# Audio.net
KiCad netlist of a schematic drawn in Altium Designer
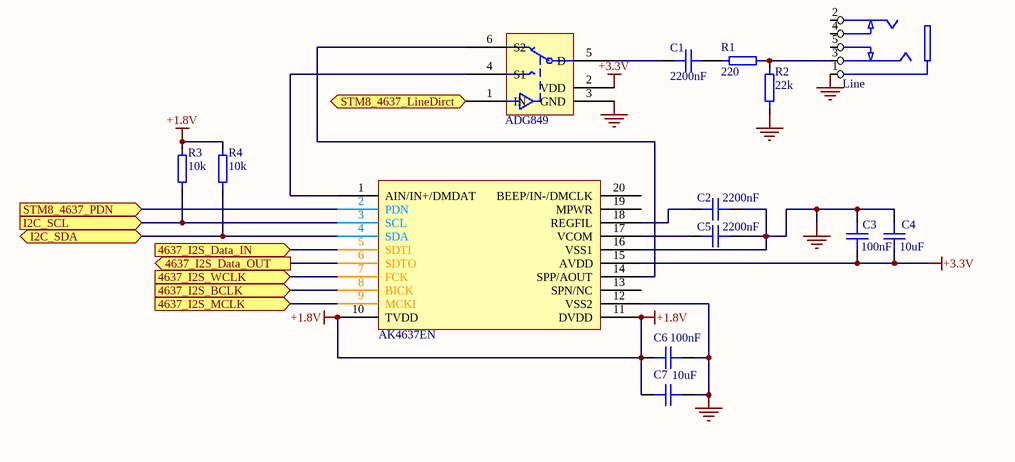
[diagram p0: Audio.SchDoc]

(export (version "E")
  (design (tool "Eeschema 10.0.6"))
  (components
    (comp (ref "ADG849") (value "ADG849") (footprint "ADG849") (libsource (lib "WPU161C") (part "ADG849")))
    (comp (ref "AK4637EN")
      (value "AK4637EN")
      (footprint "AK4637EN")
      (libsource (lib "WPU161C") (part "AK4637EN"))
    )
    (comp (ref "C1")
      (value "2200nF")
      (footprint "SMD 0402")
      (fields (field (name "Comment") "Capacity SMD"))
      (libsource (lib "WPU161C") (part "Capacity SMD"))
    )
    (comp (ref "C2")
      (value "2200nF")
      (footprint "SMD 0402")
      (fields (field (name "Comment") "Capacity SMD"))
      (libsource (lib "WPU161C") (part "Capacity SMD"))
    )
    (comp (ref "C3")
      (value "100nF")
      (footprint "SMD 0402")
      (fields (field (name "Comment") "Capacity SMD"))
      (libsource (lib "WPU161C") (part "Capacity SMD"))
    )
    (comp (ref "C4")
      (value "10uF")
      (footprint "SMD 0402")
      (fields (field (name "Comment") "Capacity SMD"))
      (libsource (lib "WPU161C") (part "Capacity SMD"))
    )
    (comp (ref "C5")
      (value "2200nF")
      (footprint "SMD 0402")
      (fields (field (name "Comment") "Capacity SMD"))
      (libsource (lib "WPU161C") (part "Capacity SMD"))
    )
    (comp (ref "C6")
      (value "100nF")
      (footprint "SMD 0402")
      (fields (field (name "Comment") "Capacity SMD"))
      (libsource (lib "WPU161C") (part "Capacity SMD"))
    )
    (comp (ref "C7")
      (value "10uF")
      (footprint "SMD 0402")
      (fields (field (name "Comment") "Capacity SMD"))
      (libsource (lib "WPU161C") (part "Capacity SMD"))
    )
    (comp (ref "Line")
      (value "Audio Jack")
      (footprint "Audio Jack PJ-328")
      (libsource (lib "WPU161C") (part "Audio Jack PJ-328"))
    )
    (comp (ref "R1")
      (value "220")
      (footprint "SMD 0402")
      (fields (field (name "Comment") "Resistor SMD"))
      (libsource (lib "WPU161C") (part "Resistor SMD"))
    )
    (comp (ref "R2")
      (value "22k")
      (footprint "SMD 0402")
      (fields (field (name "Comment") "Resistor SMD"))
      (libsource (lib "WPU161C") (part "Resistor SMD"))
    )
    (comp (ref "R3")
      (value "10k")
      (footprint "SMD 0402")
      (fields (field (name "Comment") "Resistor SMD"))
      (libsource (lib "WPU161C") (part "Resistor SMD"))
    )
    (comp (ref "R4")
      (value "10k")
      (footprint "SMD 0402")
      (fields (field (name "Comment") "Resistor SMD"))
      (libsource (lib "WPU161C") (part "Resistor SMD"))
    )
  )
  (nets
    (net (code "1") (name "+1.8V") (class "Default")
      (node (ref "AK4637EN") (pin "10") (pinfunction "TVDD_10") (pintype "passive"))
      (node (ref "AK4637EN") (pin "11") (pinfunction "DVDD_11") (pintype "passive"))
      (node (ref "C6") (pin "1") (pintype "passive"))
      (node (ref "C7") (pin "1") (pintype "passive"))
      (node (ref "R3") (pin "2") (pintype "passive"))
      (node (ref "R4") (pin "2") (pintype "passive"))
    )
    (net (code "2") (name "+3.3V") (class "Default")
      (node (ref "ADG849") (pin "2") (pinfunction "VDD_2") (pintype "passive"))
      (node (ref "AK4637EN") (pin "15") (pinfunction "AVDD_15") (pintype "passive"))
      (node (ref "C3") (pin "1") (pintype "passive"))
      (node (ref "C4") (pin "1") (pintype "passive"))
    )
    (net (code "3") (name "/4637_I2S_BCLK") (class "Default")
      (node (ref "AK4637EN") (pin "8") (pinfunction "BICK_8") (pintype "passive"))
    )
    (net (code "4") (name "/4637_I2S_Data_IN") (class "Default")
      (node (ref "AK4637EN") (pin "5") (pinfunction "SDTI_5") (pintype "passive"))
    )
    (net (code "5") (name "/4637_I2S_Data_OUT") (class "Default")
      (node (ref "AK4637EN") (pin "6") (pinfunction "SDTO_6") (pintype "passive"))
    )
    (net (code "6") (name "/4637_I2S_MCLK") (class "Default")
      (node (ref "AK4637EN") (pin "9") (pinfunction "MCKI_9") (pintype "passive"))
    )
    (net (code "7") (name "/4637_I2S_WCLK") (class "Default")
      (node (ref "AK4637EN") (pin "7") (pinfunction "FCK_7") (pintype "passive"))
    )
    (net (code "8") (name "/I2C_SCL") (class "Default")
      (node (ref "AK4637EN") (pin "3") (pinfunction "SCL_3") (pintype "passive"))
      (node (ref "R3") (pin "1") (pintype "passive"))
    )
    (net (code "9") (name "/I2C_SDA") (class "Default")
      (node (ref "AK4637EN") (pin "4") (pinfunction "SDA_4") (pintype "passive"))
      (node (ref "R4") (pin "1") (pintype "passive"))
    )
    (net (code "10") (name "/STM8_4637_LineDirct") (class "Default")
      (node (ref "ADG849") (pin "1") (pinfunction "IN_1") (pintype "passive"))
    )
    (net (code "11") (name "/STM8_4637_PDN") (class "Default")
      (node (ref "AK4637EN") (pin "2") (pinfunction "PDN_2") (pintype "passive"))
    )
    (net (code "12") (name "GND") (class "Default")
      (node (ref "ADG849") (pin "3") (pinfunction "GND_3") (pintype "passive"))
      (node (ref "AK4637EN") (pin "12") (pinfunction "VSS2_12") (pintype "passive"))
      (node (ref "AK4637EN") (pin "16") (pinfunction "VSS1_16") (pintype "passive"))
      (node (ref "C2") (pin "2") (pintype "passive"))
      (node (ref "C3") (pin "2") (pintype "passive"))
      (node (ref "C4") (pin "2") (pintype "passive"))
      (node (ref "C5") (pin "2") (pintype "passive"))
      (node (ref "C6") (pin "2") (pintype "passive"))
      (node (ref "C7") (pin "2") (pintype "passive"))
      (node (ref "Line") (pin "1") (pinfunction "GND_1") (pintype "passive"))
      (node (ref "R2") (pin "1") (pintype "passive"))
    )
    (net (code "13") (name "Net-(ADG849-D)") (class "Default")
      (node (ref "ADG849") (pin "5") (pinfunction "D_5") (pintype "passive"))
      (node (ref "C1") (pin "1") (pintype "passive"))
    )
    (net (code "14") (name "Net-(ADG849-S1)") (class "Default")
      (node (ref "ADG849") (pin "4") (pinfunction "S1_4") (pintype "passive"))
      (node (ref "AK4637EN") (pin "1") (pinfunction "AIN/IN+/DMDAT_1") (pintype "passive"))
    )
    (net (code "15") (name "Net-(ADG849-S2)") (class "Default")
      (node (ref "ADG849") (pin "6") (pinfunction "S2_6") (pintype "passive"))
      (node (ref "AK4637EN") (pin "14") (pinfunction "SPP/AOUT_14") (pintype "passive"))
    )
    (net (code "16") (name "Net-(AK4637EN-REGFIL)") (class "Default")
      (node (ref "AK4637EN") (pin "18") (pinfunction "REGFIL_18") (pintype "passive"))
      (node (ref "C2") (pin "1") (pintype "passive"))
    )
    (net (code "17") (name "Net-(AK4637EN-VCOM)") (class "Default")
      (node (ref "AK4637EN") (pin "17") (pinfunction "VCOM_17") (pintype "passive"))
      (node (ref "C5") (pin "1") (pintype "passive"))
    )
    (net (code "18") (name "Net-(C1-Pad2)") (class "Default")
      (node (ref "C1") (pin "2") (pintype "passive"))
      (node (ref "R1") (pin "1") (pintype "passive"))
    )
    (net (code "19") (name "Net-(Line-LEFT)") (class "Default")
      (node (ref "Line") (pin "3") (pinfunction "LEFT_3") (pintype "passive"))
      (node (ref "R1") (pin "2") (pintype "passive"))
      (node (ref "R2") (pin "2") (pintype "passive"))
    )
    (net (code "20") (name "unconnected-(AK4637EN-BEEP{slash}IN-{slash}DMCLK-Pad20)") (class "Default")
      (node (ref "AK4637EN") (pin "20") (pinfunction "BEEP/IN-/DMCLK_20") (pintype "passive"))
    )
    (net (code "21") (name "unconnected-(AK4637EN-MPWR-Pad19)") (class "Default")
      (node (ref "AK4637EN") (pin "19") (pinfunction "MPWR_19") (pintype "passive"))
    )
    (net (code "22") (name "unconnected-(AK4637EN-SPN{slash}NC-Pad13)") (class "Default")
      (node (ref "AK4637EN") (pin "13") (pinfunction "SPN/NC_13") (pintype "passive"))
    )
    (net (code "23") (name "unconnected-(Line-LEFT_SW-Pad5)") (class "Default")
      (node (ref "Line") (pin "5") (pinfunction "LEFT_SW_5") (pintype "passive"))
    )
    (net (code "24") (name "unconnected-(Line-RIGHT-Pad2)") (class "Default")
      (node (ref "Line") (pin "2") (pinfunction "RIGHT_2") (pintype "passive"))
    )
    (net (code "25") (name "unconnected-(Line-RIGHT_SW-Pad4)") (class "Default")
      (node (ref "Line") (pin "4") (pinfunction "RIGHT_SW_4") (pintype "passive"))
    )
  )
)
